# 05-Front_Panel_SFP_1.net
KiCad netlist of a schematic drawn in Altium Designer
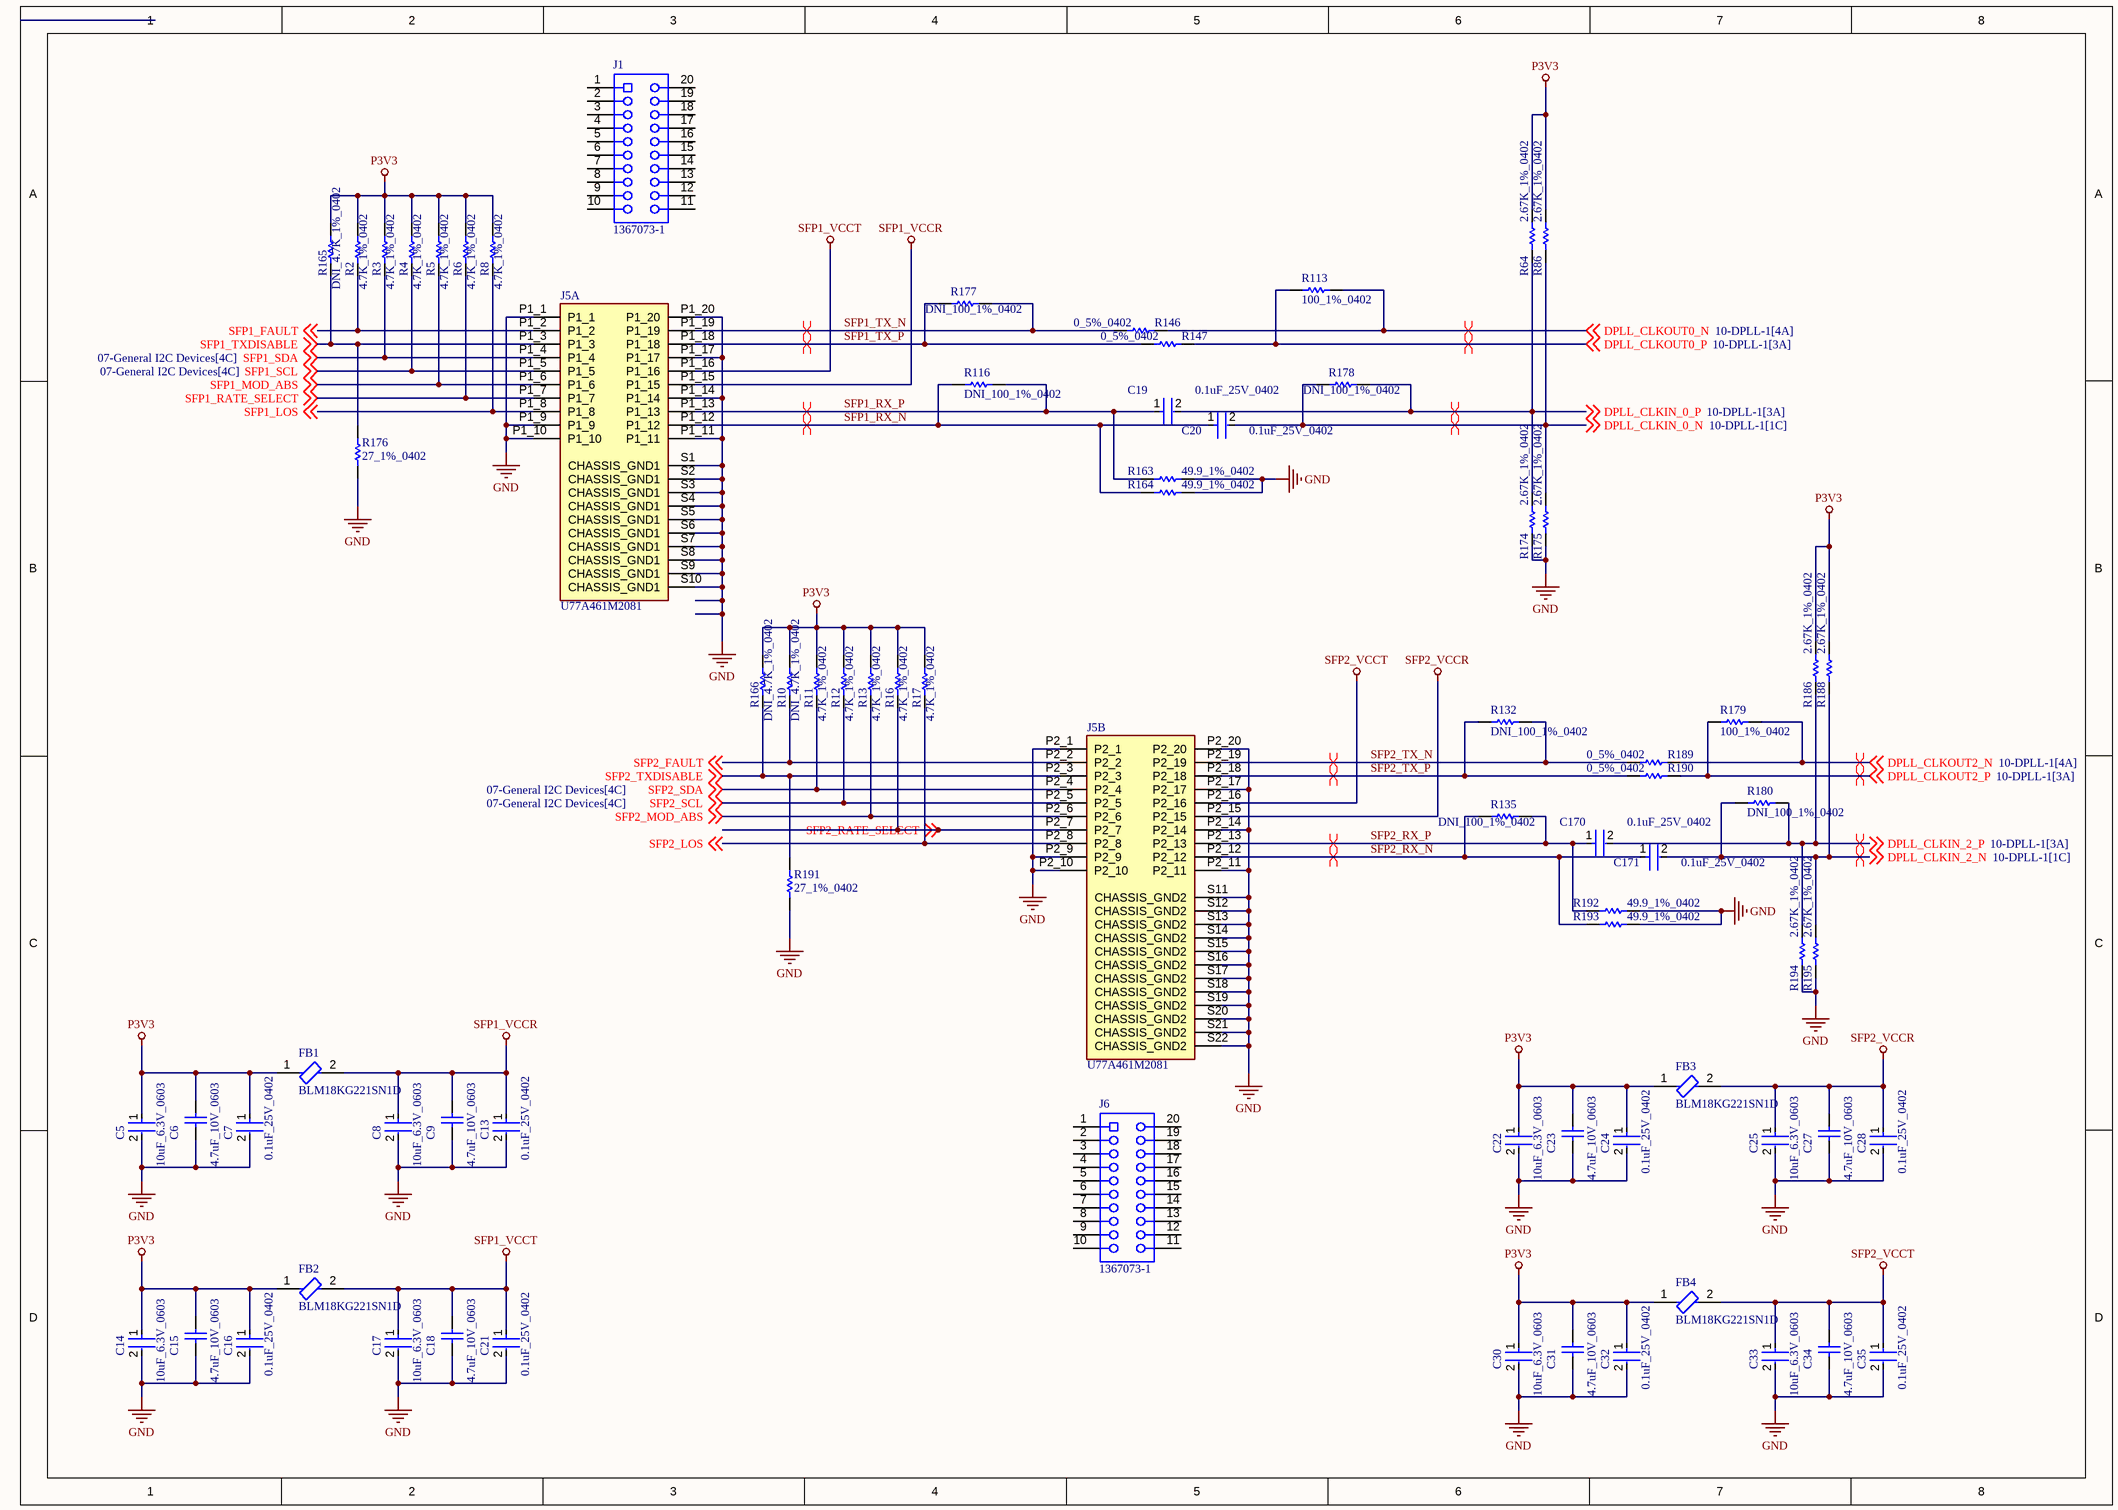
[diagram p0: 05-Front Panel SFP_1.SchDoc]

(export (version "E")
  (design (tool "Eeschema 10.0.6"))
  (components
    (comp (ref "C5")
      (value "10uF_6.3V_0603")
      (footprint "FP-C0603C106M9PACTU-MFG")
      (description "CAP CER 10UF 6.3V X5R 0603")
      (fields
        (field (name "MANUFACTURER PART NUMBER") "C0603C106M9PACTU")
        (field (name "MANUFACTURER") "Kemet")
      )
      (libsource (lib "Altium Content Vault") (part "b4654b650e69147ec39a6b967a45e02"))
    )
    (comp (ref "C6")
      (value "4.7uF_10V_0603")
      (footprint "CAPC1608X87X35NL15T15")
      (fields (field (name "PART NUMBER") "C0603C475K8PACTU") (field (name "MANUFACTURER") "Kemet"))
      (libsource (lib "Altium Content Vault") (part "CAP"))
    )
    (comp (ref "C7")
      (value "0.1uF_25V_0402")
      (footprint "FP-0402-L_1_0_1-W_0_5_0_1-IPC_C")
      (description "General Purpose Ceramic Capacitor, 0402, 100nF, 10%, X7R, 15%, 25V")
      (fields (field (name "VOLTAGE") "25V") (field (name "TOLERANCE") "10%"))
      (libsource (lib "Altium Content Vault") (part "b4654b650e69147ec39a6b967a45e02"))
    )
    (comp (ref "C8")
      (value "10uF_6.3V_0603")
      (footprint "FP-C0603C106M9PACTU-MFG")
      (description "CAP CER 10UF 6.3V X5R 0603")
      (fields
        (field (name "MANUFACTURER PART NUMBER") "C0603C106M9PACTU")
        (field (name "MANUFACTURER") "Kemet")
      )
      (libsource (lib "Altium Content Vault") (part "b4654b650e69147ec39a6b967a45e02"))
    )
    (comp (ref "C9")
      (value "4.7uF_10V_0603")
      (footprint "CAPC1608X87X35NL15T15")
      (fields (field (name "PART NUMBER") "C0603C475K8PACTU") (field (name "MANUFACTURER") "Kemet"))
      (libsource (lib "Altium Content Vault") (part "CAP"))
    )
    (comp (ref "C13")
      (value "0.1uF_25V_0402")
      (footprint "FP-0402-L_1_0_1-W_0_5_0_1-IPC_C")
      (description "General Purpose Ceramic Capacitor, 0402, 100nF, 10%, X7R, 15%, 25V")
      (fields (field (name "VOLTAGE") "25V") (field (name "TOLERANCE") "10%"))
      (libsource (lib "Altium Content Vault") (part "b4654b650e69147ec39a6b967a45e02"))
    )
    (comp (ref "C14")
      (value "10uF_6.3V_0603")
      (footprint "FP-C0603C106M9PACTU-MFG")
      (description "CAP CER 10UF 6.3V X5R 0603")
      (fields
        (field (name "MANUFACTURER PART NUMBER") "C0603C106M9PACTU")
        (field (name "MANUFACTURER") "Kemet")
      )
      (libsource (lib "Altium Content Vault") (part "b4654b650e69147ec39a6b967a45e02"))
    )
    (comp (ref "C15")
      (value "4.7uF_10V_0603")
      (footprint "CAPC1608X87X35NL15T15")
      (fields (field (name "PART NUMBER") "C0603C475K8PACTU") (field (name "MANUFACTURER") "Kemet"))
      (libsource (lib "Altium Content Vault") (part "CAP"))
    )
    (comp (ref "C16")
      (value "0.1uF_25V_0402")
      (footprint "FP-0402-L_1_0_1-W_0_5_0_1-IPC_C")
      (description "General Purpose Ceramic Capacitor, 0402, 100nF, 10%, X7R, 15%, 25V")
      (fields (field (name "VOLTAGE") "25V") (field (name "TOLERANCE") "10%"))
      (libsource (lib "Altium Content Vault") (part "b4654b650e69147ec39a6b967a45e02"))
    )
    (comp (ref "C17")
      (value "10uF_6.3V_0603")
      (footprint "FP-C0603C106M9PACTU-MFG")
      (description "CAP CER 10UF 6.3V X5R 0603")
      (fields
        (field (name "MANUFACTURER PART NUMBER") "C0603C106M9PACTU")
        (field (name "MANUFACTURER") "Kemet")
      )
      (libsource (lib "Altium Content Vault") (part "b4654b650e69147ec39a6b967a45e02"))
    )
    (comp (ref "C18")
      (value "4.7uF_10V_0603")
      (footprint "CAPC1608X87X35NL15T15")
      (fields (field (name "PART NUMBER") "C0603C475K8PACTU") (field (name "MANUFACTURER") "Kemet"))
      (libsource (lib "Altium Content Vault") (part "CAP"))
    )
    (comp (ref "C19")
      (value "0.1uF_25V_0402")
      (footprint "FP-0402-L_1_0_1-W_0_5_0_1-IPC_C")
      (description "General Purpose Ceramic Capacitor, 0402, 100nF, 10%, X7R, 15%, 25V")
      (fields (field (name "VOLTAGE") "25V") (field (name "TOLERANCE") "10%"))
      (libsource (lib "Altium Content Vault") (part "b4654b650e69147ec39a6b967a45e02"))
    )
    (comp (ref "C20")
      (value "0.1uF_25V_0402")
      (footprint "FP-0402-L_1_0_1-W_0_5_0_1-IPC_C")
      (description "General Purpose Ceramic Capacitor, 0402, 100nF, 10%, X7R, 15%, 25V")
      (fields (field (name "VOLTAGE") "25V") (field (name "TOLERANCE") "10%"))
      (libsource (lib "Altium Content Vault") (part "b4654b650e69147ec39a6b967a45e02"))
    )
    (comp (ref "C21")
      (value "0.1uF_25V_0402")
      (footprint "FP-0402-L_1_0_1-W_0_5_0_1-IPC_C")
      (description "General Purpose Ceramic Capacitor, 0402, 100nF, 10%, X7R, 15%, 25V")
      (fields (field (name "VOLTAGE") "25V") (field (name "TOLERANCE") "10%"))
      (libsource (lib "Altium Content Vault") (part "b4654b650e69147ec39a6b967a45e02"))
    )
    (comp (ref "C22")
      (value "10uF_6.3V_0603")
      (footprint "FP-C0603C106M9PACTU-MFG")
      (description "CAP CER 10UF 6.3V X5R 0603")
      (fields
        (field (name "MANUFACTURER PART NUMBER") "C0603C106M9PACTU")
        (field (name "MANUFACTURER") "Kemet")
      )
      (libsource (lib "Altium Content Vault") (part "b4654b650e69147ec39a6b967a45e02"))
    )
    (comp (ref "C23")
      (value "4.7uF_10V_0603")
      (footprint "CAPC1608X87X35NL15T15")
      (fields (field (name "PART NUMBER") "C0603C475K8PACTU") (field (name "MANUFACTURER") "Kemet"))
      (libsource (lib "Altium Content Vault") (part "CAP"))
    )
    (comp (ref "C24")
      (value "0.1uF_25V_0402")
      (footprint "FP-0402-L_1_0_1-W_0_5_0_1-IPC_C")
      (description "General Purpose Ceramic Capacitor, 0402, 100nF, 10%, X7R, 15%, 25V")
      (fields (field (name "VOLTAGE") "25V") (field (name "TOLERANCE") "10%"))
      (libsource (lib "Altium Content Vault") (part "b4654b650e69147ec39a6b967a45e02"))
    )
    (comp (ref "C25")
      (value "10uF_6.3V_0603")
      (footprint "FP-C0603C106M9PACTU-MFG")
      (description "CAP CER 10UF 6.3V X5R 0603")
      (fields
        (field (name "MANUFACTURER PART NUMBER") "C0603C106M9PACTU")
        (field (name "MANUFACTURER") "Kemet")
      )
      (libsource (lib "Altium Content Vault") (part "b4654b650e69147ec39a6b967a45e02"))
    )
    (comp (ref "C27")
      (value "4.7uF_10V_0603")
      (footprint "CAPC1608X87X35NL15T15")
      (fields (field (name "PART NUMBER") "C0603C475K8PACTU") (field (name "MANUFACTURER") "Kemet"))
      (libsource (lib "Altium Content Vault") (part "CAP"))
    )
    (comp (ref "C28")
      (value "0.1uF_25V_0402")
      (footprint "FP-0402-L_1_0_1-W_0_5_0_1-IPC_C")
      (description "General Purpose Ceramic Capacitor, 0402, 100nF, 10%, X7R, 15%, 25V")
      (fields (field (name "VOLTAGE") "25V") (field (name "TOLERANCE") "10%"))
      (libsource (lib "Altium Content Vault") (part "b4654b650e69147ec39a6b967a45e02"))
    )
    (comp (ref "C30")
      (value "10uF_6.3V_0603")
      (footprint "FP-C0603C106M9PACTU-MFG")
      (description "CAP CER 10UF 6.3V X5R 0603")
      (fields
        (field (name "MANUFACTURER PART NUMBER") "C0603C106M9PACTU")
        (field (name "MANUFACTURER") "Kemet")
      )
      (libsource (lib "Altium Content Vault") (part "b4654b650e69147ec39a6b967a45e02"))
    )
    (comp (ref "C31")
      (value "4.7uF_10V_0603")
      (footprint "CAPC1608X87X35NL15T15")
      (fields (field (name "PART NUMBER") "C0603C475K8PACTU") (field (name "MANUFACTURER") "Kemet"))
      (libsource (lib "Altium Content Vault") (part "CAP"))
    )
    (comp (ref "C32")
      (value "0.1uF_25V_0402")
      (footprint "FP-0402-L_1_0_1-W_0_5_0_1-IPC_C")
      (description "General Purpose Ceramic Capacitor, 0402, 100nF, 10%, X7R, 15%, 25V")
      (fields (field (name "VOLTAGE") "25V") (field (name "TOLERANCE") "10%"))
      (libsource (lib "Altium Content Vault") (part "b4654b650e69147ec39a6b967a45e02"))
    )
    (comp (ref "C33")
      (value "10uF_6.3V_0603")
      (footprint "FP-C0603C106M9PACTU-MFG")
      (description "CAP CER 10UF 6.3V X5R 0603")
      (fields
        (field (name "MANUFACTURER PART NUMBER") "C0603C106M9PACTU")
        (field (name "MANUFACTURER") "Kemet")
      )
      (libsource (lib "Altium Content Vault") (part "b4654b650e69147ec39a6b967a45e02"))
    )
    (comp (ref "C34")
      (value "4.7uF_10V_0603")
      (footprint "CAPC1608X87X35NL15T15")
      (fields (field (name "PART NUMBER") "C0603C475K8PACTU") (field (name "MANUFACTURER") "Kemet"))
      (libsource (lib "Altium Content Vault") (part "CAP"))
    )
    (comp (ref "C35")
      (value "0.1uF_25V_0402")
      (footprint "FP-0402-L_1_0_1-W_0_5_0_1-IPC_C")
      (description "General Purpose Ceramic Capacitor, 0402, 100nF, 10%, X7R, 15%, 25V")
      (fields (field (name "VOLTAGE") "25V") (field (name "TOLERANCE") "10%"))
      (libsource (lib "Altium Content Vault") (part "b4654b650e69147ec39a6b967a45e02"))
    )
    (comp (ref "C170")
      (value "0.1uF_25V_0402")
      (footprint "FP-0402-L_1_0_1-W_0_5_0_1-IPC_C")
      (description "General Purpose Ceramic Capacitor, 0402, 100nF, 10%, X7R, 15%, 25V")
      (fields (field (name "VOLTAGE") "25V") (field (name "TOLERANCE") "10%"))
      (libsource (lib "Altium Content Vault") (part "b4654b650e69147ec39a6b967a45e02"))
    )
    (comp (ref "C171")
      (value "0.1uF_25V_0402")
      (footprint "FP-0402-L_1_0_1-W_0_5_0_1-IPC_C")
      (description "General Purpose Ceramic Capacitor, 0402, 100nF, 10%, X7R, 15%, 25V")
      (fields (field (name "VOLTAGE") "25V") (field (name "TOLERANCE") "10%"))
      (libsource (lib "Altium Content Vault") (part "b4654b650e69147ec39a6b967a45e02"))
    )
    (comp (ref "FB1")
      (value "BLM18KG221SN1D")
      (footprint "FP-BLM18-0_15-t0_8-IPC_B")
      (description "Chip Ferrite Bead, 0603, 220Ω @ 100MHz, 0.05Ω, 25%, 2.2A")
      (fields (field (name "TOLERANCE") "25%"))
      (libsource (lib "Altium Content Vault") (part "5f30dd21d616792df468990f7003faa"))
    )
    (comp (ref "FB2")
      (value "BLM18KG221SN1D")
      (footprint "FP-BLM18-0_15-t0_8-IPC_B")
      (description "Chip Ferrite Bead, 0603, 220Ω @ 100MHz, 0.05Ω, 25%, 2.2A")
      (fields (field (name "TOLERANCE") "25%"))
      (libsource (lib "Altium Content Vault") (part "5f30dd21d616792df468990f7003faa"))
    )
    (comp (ref "FB3")
      (value "BLM18KG221SN1D")
      (footprint "FP-BLM18-0_15-t0_8-IPC_B")
      (description "Chip Ferrite Bead, 0603, 220Ω @ 100MHz, 0.05Ω, 25%, 2.2A")
      (fields (field (name "TOLERANCE") "25%"))
      (libsource (lib "Altium Content Vault") (part "5f30dd21d616792df468990f7003faa"))
    )
    (comp (ref "FB4")
      (value "BLM18KG221SN1D")
      (footprint "FP-BLM18-0_15-t0_8-IPC_B")
      (description "Chip Ferrite Bead, 0603, 220Ω @ 100MHz, 0.05Ω, 25%, 2.2A")
      (fields (field (name "TOLERANCE") "25%"))
      (libsource (lib "Altium Content Vault") (part "5f30dd21d616792df468990f7003faa"))
    )
    (comp (ref "J1")
      (value "1367073-1")
      (footprint "TECO-1367073-1_V")
      (fields (field (name "MANUFACTURER") "TE Connectivity"))
      (libsource (lib "Altium Content Vault") (part "CN-2P-F-R20_B"))
    )
    (comp (ref "J5")
      (value "U77A461M2081")
      (footprint "AMPHENOL_U77A461M2081")
      (fields (field (name "MF") "AMPHENOL ICC / FCI"))
      (libsource (lib "U77A461M2081") (part "U77A461M2081"))
    )
    (comp (ref "J6")
      (value "1367073-1")
      (footprint "TECO-1367073-1_V")
      (fields (field (name "MANUFACTURER") "TE Connectivity"))
      (libsource (lib "Altium Content Vault") (part "CN-2P-F-R20_B"))
    )
    (comp (ref "R2")
      (value "4.7K_1%_0402")
      (footprint "RESC1005X40X25NL10T10")
      (fields (field (name "MANUFACTURER") "Bourns") (field (name "PART NUMBER") "CR0402-FX-4701GLF"))
      (libsource (lib "Altium Content Vault") (part "RES"))
    )
    (comp (ref "R3")
      (value "4.7K_1%_0402")
      (footprint "RESC1005X40X25NL10T10")
      (fields (field (name "MANUFACTURER") "Bourns") (field (name "PART NUMBER") "CR0402-FX-4701GLF"))
      (libsource (lib "Altium Content Vault") (part "RES"))
    )
    (comp (ref "R4")
      (value "4.7K_1%_0402")
      (footprint "RESC1005X40X25NL10T10")
      (fields (field (name "MANUFACTURER") "Bourns") (field (name "PART NUMBER") "CR0402-FX-4701GLF"))
      (libsource (lib "Altium Content Vault") (part "RES"))
    )
    (comp (ref "R5")
      (value "4.7K_1%_0402")
      (footprint "RESC1005X40X25NL10T10")
      (fields (field (name "MANUFACTURER") "Bourns") (field (name "PART NUMBER") "CR0402-FX-4701GLF"))
      (libsource (lib "Altium Content Vault") (part "RES"))
    )
    (comp (ref "R6")
      (value "4.7K_1%_0402")
      (footprint "RESC1005X40X25NL10T10")
      (fields (field (name "MANUFACTURER") "Bourns") (field (name "PART NUMBER") "CR0402-FX-4701GLF"))
      (libsource (lib "Altium Content Vault") (part "RES"))
    )
    (comp (ref "R8")
      (value "4.7K_1%_0402")
      (footprint "RESC1005X40X25NL10T10")
      (fields (field (name "MANUFACTURER") "Bourns") (field (name "PART NUMBER") "CR0402-FX-4701GLF"))
      (libsource (lib "Altium Content Vault") (part "RES"))
    )
    (comp (ref "R10")
      (value "DNI_4.7K_1%_0402")
      (footprint "RESC1005X40X25NL10T10")
      (fields (field (name "MANUFACTURER") "Bourns") (field (name "PART NUMBER") "CR0402-FX-4701GLF"))
      (libsource (lib "Altium Content Vault") (part "RES"))
    )
    (comp (ref "R11")
      (value "4.7K_1%_0402")
      (footprint "RESC1005X40X25NL10T10")
      (fields (field (name "MANUFACTURER") "Bourns") (field (name "PART NUMBER") "CR0402-FX-4701GLF"))
      (libsource (lib "Altium Content Vault") (part "RES"))
    )
    (comp (ref "R12")
      (value "4.7K_1%_0402")
      (footprint "RESC1005X40X25NL10T10")
      (fields (field (name "MANUFACTURER") "Bourns") (field (name "PART NUMBER") "CR0402-FX-4701GLF"))
      (libsource (lib "Altium Content Vault") (part "RES"))
    )
    (comp (ref "R13")
      (value "4.7K_1%_0402")
      (footprint "RESC1005X40X25NL10T10")
      (fields (field (name "MANUFACTURER") "Bourns") (field (name "PART NUMBER") "CR0402-FX-4701GLF"))
      (libsource (lib "Altium Content Vault") (part "RES"))
    )
    (comp (ref "R16")
      (value "4.7K_1%_0402")
      (footprint "RESC1005X40X25NL10T10")
      (fields (field (name "MANUFACTURER") "Bourns") (field (name "PART NUMBER") "CR0402-FX-4701GLF"))
      (libsource (lib "Altium Content Vault") (part "RES"))
    )
    (comp (ref "R17")
      (value "4.7K_1%_0402")
      (footprint "RESC1005X40X25NL10T10")
      (fields (field (name "MANUFACTURER") "Bourns") (field (name "PART NUMBER") "CR0402-FX-4701GLF"))
      (libsource (lib "Altium Content Vault") (part "RES"))
    )
    (comp (ref "R64")
      (value "2.67K_1%_0402")
      (footprint "RESC1005X40X25NL05T10")
      (fields (field (name "MANUFACTURER") "Yageo") (field (name "PART NUMBER") "RC0402FR-072K67L"))
      (libsource (lib "Altium Content Vault") (part "RES"))
    )
    (comp (ref "R86")
      (value "2.67K_1%_0402")
      (footprint "RESC1005X40X25NL05T10")
      (fields (field (name "MANUFACTURER") "Yageo") (field (name "PART NUMBER") "RC0402FR-072K67L"))
      (libsource (lib "Altium Content Vault") (part "RES"))
    )
    (comp (ref "R113")
      (value "100_1%_0402")
      (footprint "RESC1005X40X25NL05T10")
      (fields (field (name "MANUFACTURER") "Yageo") (field (name "PART NUMBER") "RC0402FR-13100RL"))
      (libsource (lib "Altium Content Vault") (part "RES"))
    )
    (comp (ref "R116")
      (value "DNI_100_1%_0402")
      (footprint "RESC1005X40X25NL05T10")
      (fields (field (name "MANUFACTURER") "Yageo") (field (name "PART NUMBER") "RC0402FR-13100RL"))
      (libsource (lib "Altium Content Vault") (part "RES"))
    )
    (comp (ref "R132")
      (value "DNI_100_1%_0402")
      (footprint "RESC1005X40X25NL05T10")
      (fields (field (name "MANUFACTURER") "Yageo") (field (name "PART NUMBER") "RC0402FR-13100RL"))
      (libsource (lib "Altium Content Vault") (part "RES"))
    )
    (comp (ref "R135")
      (value "DNI_100_1%_0402")
      (footprint "RESC1005X40X25NL05T10")
      (fields (field (name "MANUFACTURER") "Yageo") (field (name "PART NUMBER") "RC0402FR-13100RL"))
      (libsource (lib "Altium Content Vault") (part "RES"))
    )
    (comp (ref "R146")
      (value "0_5%_0402")
      (footprint "RESC1005X40X25LL10T10")
      (fields (field (name "MANUFACTURER") "KOA Speer") (field (name "PART NUMBER") "RK73Z1ETTP"))
      (libsource (lib "Altium Content Vault") (part "RES"))
    )
    (comp (ref "R147")
      (value "0_5%_0402")
      (footprint "RESC1005X40X25LL10T10")
      (fields (field (name "MANUFACTURER") "KOA Speer") (field (name "PART NUMBER") "RK73Z1ETTP"))
      (libsource (lib "Altium Content Vault") (part "RES"))
    )
    (comp (ref "R163")
      (value "49.9_1%_0402")
      (footprint "RESC1005X40X25NL10T10")
      (fields (field (name "PART NUMBER") "RK73H1ETTP49R9F") (field (name "MANUFACTURER") "KOA Speer"))
      (libsource (lib "Altium Content Vault") (part "RES"))
    )
    (comp (ref "R164")
      (value "49.9_1%_0402")
      (footprint "RESC1005X40X25NL10T10")
      (fields (field (name "PART NUMBER") "RK73H1ETTP49R9F") (field (name "MANUFACTURER") "KOA Speer"))
      (libsource (lib "Altium Content Vault") (part "RES"))
    )
    (comp (ref "R165")
      (value "DNI_4.7K_1%_0402")
      (footprint "RESC1005X40X25NL10T10")
      (fields (field (name "MANUFACTURER") "Bourns") (field (name "PART NUMBER") "CR0402-FX-4701GLF"))
      (libsource (lib "Altium Content Vault") (part "RES"))
    )
    (comp (ref "R166")
      (value "DNI_4.7K_1%_0402")
      (footprint "RESC1005X40X25NL10T10")
      (fields (field (name "MANUFACTURER") "Bourns") (field (name "PART NUMBER") "CR0402-FX-4701GLF"))
      (libsource (lib "Altium Content Vault") (part "RES"))
    )
    (comp (ref "R174")
      (value "2.67K_1%_0402")
      (footprint "RESC1005X40X25NL05T10")
      (fields (field (name "MANUFACTURER") "Yageo") (field (name "PART NUMBER") "RC0402FR-072K67L"))
      (libsource (lib "Altium Content Vault") (part "RES"))
    )
    (comp (ref "R175")
      (value "2.67K_1%_0402")
      (footprint "RESC1005X40X25NL05T10")
      (fields (field (name "MANUFACTURER") "Yageo") (field (name "PART NUMBER") "RC0402FR-072K67L"))
      (libsource (lib "Altium Content Vault") (part "RES"))
    )
    (comp (ref "R176")
      (value "27_1%_0402")
      (footprint "RESC1005X40X25NL05T05")
      (fields (field (name "PART NUMBER") "CRCW040227R0FKED") (field (name "MANUFACTURER") "Vishay Dale"))
      (libsource (lib "Altium Content Vault") (part "RES"))
    )
    (comp (ref "R177")
      (value "DNI_100_1%_0402")
      (footprint "RESC1005X40X25NL05T10")
      (fields (field (name "MANUFACTURER") "Yageo") (field (name "PART NUMBER") "RC0402FR-13100RL"))
      (libsource (lib "Altium Content Vault") (part "RES"))
    )
    (comp (ref "R178")
      (value "DNI_100_1%_0402")
      (footprint "RESC1005X40X25NL05T10")
      (fields (field (name "MANUFACTURER") "Yageo") (field (name "PART NUMBER") "RC0402FR-13100RL"))
      (libsource (lib "Altium Content Vault") (part "RES"))
    )
    (comp (ref "R179")
      (value "100_1%_0402")
      (footprint "RESC1005X40X25NL05T10")
      (fields (field (name "MANUFACTURER") "Yageo") (field (name "PART NUMBER") "RC0402FR-13100RL"))
      (libsource (lib "Altium Content Vault") (part "RES"))
    )
    (comp (ref "R180")
      (value "DNI_100_1%_0402")
      (footprint "RESC1005X40X25NL05T10")
      (fields (field (name "MANUFACTURER") "Yageo") (field (name "PART NUMBER") "RC0402FR-13100RL"))
      (libsource (lib "Altium Content Vault") (part "RES"))
    )
    (comp (ref "R186")
      (value "2.67K_1%_0402")
      (footprint "RESC1005X40X25NL05T10")
      (fields (field (name "MANUFACTURER") "Yageo") (field (name "PART NUMBER") "RC0402FR-072K67L"))
      (libsource (lib "Altium Content Vault") (part "RES"))
    )
    (comp (ref "R188")
      (value "2.67K_1%_0402")
      (footprint "RESC1005X40X25NL05T10")
      (fields (field (name "MANUFACTURER") "Yageo") (field (name "PART NUMBER") "RC0402FR-072K67L"))
      (libsource (lib "Altium Content Vault") (part "RES"))
    )
    (comp (ref "R189")
      (value "0_5%_0402")
      (footprint "RESC1005X40X25LL10T10")
      (fields (field (name "MANUFACTURER") "KOA Speer") (field (name "PART NUMBER") "RK73Z1ETTP"))
      (libsource (lib "Altium Content Vault") (part "RES"))
    )
    (comp (ref "R190")
      (value "0_5%_0402")
      (footprint "RESC1005X40X25LL10T10")
      (fields (field (name "MANUFACTURER") "KOA Speer") (field (name "PART NUMBER") "RK73Z1ETTP"))
      (libsource (lib "Altium Content Vault") (part "RES"))
    )
    (comp (ref "R191")
      (value "27_1%_0402")
      (footprint "RESC1005X40X25NL05T05")
      (fields (field (name "PART NUMBER") "CRCW040227R0FKED") (field (name "MANUFACTURER") "Vishay Dale"))
      (libsource (lib "Altium Content Vault") (part "RES"))
    )
    (comp (ref "R192")
      (value "49.9_1%_0402")
      (footprint "RESC1005X40X25NL10T10")
      (fields (field (name "PART NUMBER") "RK73H1ETTP49R9F") (field (name "MANUFACTURER") "KOA Speer"))
      (libsource (lib "Altium Content Vault") (part "RES"))
    )
    (comp (ref "R193")
      (value "49.9_1%_0402")
      (footprint "RESC1005X40X25NL10T10")
      (fields (field (name "PART NUMBER") "RK73H1ETTP49R9F") (field (name "MANUFACTURER") "KOA Speer"))
      (libsource (lib "Altium Content Vault") (part "RES"))
    )
    (comp (ref "R194")
      (value "2.67K_1%_0402")
      (footprint "RESC1005X40X25NL05T10")
      (fields (field (name "MANUFACTURER") "Yageo") (field (name "PART NUMBER") "RC0402FR-072K67L"))
      (libsource (lib "Altium Content Vault") (part "RES"))
    )
    (comp (ref "R195")
      (value "2.67K_1%_0402")
      (footprint "RESC1005X40X25NL05T10")
      (fields (field (name "MANUFACTURER") "Yageo") (field (name "PART NUMBER") "RC0402FR-072K67L"))
      (libsource (lib "Altium Content Vault") (part "RES"))
    )
  )
  (nets
    (net (code "1") (name "/SFP1_RX_N") (class "Default")
      (node (ref "C20") (pin "1") (pinfunction "1_1") (pintype "passive"))
      (node (ref "J5") (pin "P1_12") (pinfunction "P1_12_P1_12") (pintype "passive"))
      (node (ref "R116") (pin "1") (pinfunction "1_1") (pintype "passive"))
      (node (ref "R164") (pin "1") (pinfunction "1_1") (pintype "passive"))
    )
    (net (code "2") (name "/SFP1_RX_P") (class "Default")
      (node (ref "C19") (pin "1") (pinfunction "1_1") (pintype "passive"))
      (node (ref "J5") (pin "P1_13") (pinfunction "P1_13_P1_13") (pintype "passive"))
      (node (ref "R116") (pin "2") (pinfunction "2_2") (pintype "passive"))
      (node (ref "R163") (pin "1") (pinfunction "1_1") (pintype "passive"))
    )
    (net (code "3") (name "/SFP1_TX_N") (class "Default")
      (node (ref "J5") (pin "P1_19") (pinfunction "P1_19_P1_19") (pintype "passive"))
      (node (ref "R146") (pin "1") (pinfunction "1_1") (pintype "passive"))
      (node (ref "R177") (pin "2") (pinfunction "2_2") (pintype "passive"))
    )
    (net (code "4") (name "/SFP1_TX_P") (class "Default")
      (node (ref "J5") (pin "P1_18") (pinfunction "P1_18_P1_18") (pintype "passive"))
      (node (ref "R147") (pin "1") (pinfunction "1_1") (pintype "passive"))
      (node (ref "R177") (pin "1") (pinfunction "1_1") (pintype "passive"))
    )
    (net (code "5") (name "/SFP2_RX_N") (class "Default")
      (node (ref "C171") (pin "1") (pinfunction "1_1") (pintype "passive"))
      (node (ref "J5") (pin "P2_12") (pinfunction "P2_12_P2_12") (pintype "passive"))
      (node (ref "R135") (pin "1") (pinfunction "1_1") (pintype "passive"))
      (node (ref "R193") (pin "1") (pinfunction "1_1") (pintype "passive"))
    )
    (net (code "6") (name "/SFP2_RX_P") (class "Default")
      (node (ref "C170") (pin "1") (pinfunction "1_1") (pintype "passive"))
      (node (ref "J5") (pin "P2_13") (pinfunction "P2_13_P2_13") (pintype "passive"))
      (node (ref "R135") (pin "2") (pinfunction "2_2") (pintype "passive"))
      (node (ref "R192") (pin "1") (pinfunction "1_1") (pintype "passive"))
    )
    (net (code "7") (name "/SFP2_TX_N") (class "Default")
      (node (ref "J5") (pin "P2_19") (pinfunction "P2_19_P2_19") (pintype "passive"))
      (node (ref "R132") (pin "2") (pinfunction "2_2") (pintype "passive"))
      (node (ref "R189") (pin "1") (pinfunction "1_1") (pintype "passive"))
    )
    (net (code "8") (name "/SFP2_TX_P") (class "Default")
      (node (ref "J5") (pin "P2_18") (pinfunction "P2_18_P2_18") (pintype "passive"))
      (node (ref "R132") (pin "1") (pinfunction "1_1") (pintype "passive"))
      (node (ref "R190") (pin "1") (pinfunction "1_1") (pintype "passive"))
    )
    (net (code "9") (name "DPLL_CLKIN_0_N") (class "Default")
      (node (ref "C20") (pin "2") (pinfunction "2_2") (pintype "passive"))
      (node (ref "R175") (pin "2") (pinfunction "2_2") (pintype "passive"))
      (node (ref "R178") (pin "1") (pinfunction "1_1") (pintype "passive"))
      (node (ref "R86") (pin "1") (pinfunction "1_1") (pintype "passive"))
    )
    (net (code "10") (name "DPLL_CLKIN_0_P") (class "Default")
      (node (ref "C19") (pin "2") (pinfunction "2_2") (pintype "passive"))
      (node (ref "R174") (pin "2") (pinfunction "2_2") (pintype "passive"))
      (node (ref "R178") (pin "2") (pinfunction "2_2") (pintype "passive"))
      (node (ref "R64") (pin "1") (pinfunction "1_1") (pintype "passive"))
    )
    (net (code "11") (name "DPLL_CLKIN_2_N") (class "Default")
      (node (ref "C171") (pin "2") (pinfunction "2_2") (pintype "passive"))
      (node (ref "R180") (pin "1") (pinfunction "1_1") (pintype "passive"))
      (node (ref "R188") (pin "1") (pinfunction "1_1") (pintype "passive"))
      (node (ref "R195") (pin "2") (pinfunction "2_2") (pintype "passive"))
    )
    (net (code "12") (name "DPLL_CLKIN_2_P") (class "Default")
      (node (ref "C170") (pin "2") (pinfunction "2_2") (pintype "passive"))
      (node (ref "R180") (pin "2") (pinfunction "2_2") (pintype "passive"))
      (node (ref "R186") (pin "1") (pinfunction "1_1") (pintype "passive"))
      (node (ref "R194") (pin "2") (pinfunction "2_2") (pintype "passive"))
    )
    (net (code "13") (name "DPLL_CLKOUT0_N") (class "Default")
      (node (ref "R113") (pin "2") (pinfunction "2_2") (pintype "passive"))
      (node (ref "R146") (pin "2") (pinfunction "2_2") (pintype "passive"))
    )
    (net (code "14") (name "DPLL_CLKOUT0_P") (class "Default")
      (node (ref "R113") (pin "1") (pinfunction "1_1") (pintype "passive"))
      (node (ref "R147") (pin "2") (pinfunction "2_2") (pintype "passive"))
    )
    (net (code "15") (name "DPLL_CLKOUT2_N") (class "Default")
      (node (ref "R179") (pin "2") (pinfunction "2_2") (pintype "passive"))
      (node (ref "R189") (pin "2") (pinfunction "2_2") (pintype "passive"))
    )
    (net (code "16") (name "DPLL_CLKOUT2_P") (class "Default")
      (node (ref "R179") (pin "1") (pinfunction "1_1") (pintype "passive"))
      (node (ref "R190") (pin "2") (pinfunction "2_2") (pintype "passive"))
    )
    (net (code "17") (name "GND") (class "Default")
      (node (ref "C13") (pin "2") (pinfunction "2_2") (pintype "passive"))
      (node (ref "C14") (pin "2") (pinfunction "2_2") (pintype "passive"))
      (node (ref "C15") (pin "1") (pinfunction "1_1") (pintype "passive"))
      (node (ref "C16") (pin "2") (pinfunction "2_2") (pintype "passive"))
      (node (ref "C17") (pin "2") (pinfunction "2_2") (pintype "passive"))
      (node (ref "C18") (pin "1") (pinfunction "1_1") (pintype "passive"))
      (node (ref "C21") (pin "2") (pinfunction "2_2") (pintype "passive"))
      (node (ref "C22") (pin "2") (pinfunction "2_2") (pintype "passive"))
      (node (ref "C23") (pin "1") (pinfunction "1_1") (pintype "passive"))
      (node (ref "C24") (pin "2") (pinfunction "2_2") (pintype "passive"))
      (node (ref "C25") (pin "2") (pinfunction "2_2") (pintype "passive"))
      (node (ref "C27") (pin "1") (pinfunction "1_1") (pintype "passive"))
      (node (ref "C28") (pin "2") (pinfunction "2_2") (pintype "passive"))
      (node (ref "C30") (pin "2") (pinfunction "2_2") (pintype "passive"))
      (node (ref "C31") (pin "1") (pinfunction "1_1") (pintype "passive"))
      (node (ref "C32") (pin "2") (pinfunction "2_2") (pintype "passive"))
      (node (ref "C33") (pin "2") (pinfunction "2_2") (pintype "passive"))
      (node (ref "C34") (pin "1") (pinfunction "1_1") (pintype "passive"))
      (node (ref "C35") (pin "2") (pinfunction "2_2") (pintype "passive"))
      (node (ref "C5") (pin "2") (pinfunction "2_2") (pintype "passive"))
      (node (ref "C6") (pin "1") (pinfunction "1_1") (pintype "passive"))
      (node (ref "C7") (pin "2") (pinfunction "2_2") (pintype "passive"))
      (node (ref "C8") (pin "2") (pinfunction "2_2") (pintype "passive"))
      (node (ref "C9") (pin "1") (pinfunction "1_1") (pintype "passive"))
      (node (ref "J5") (pin "P1_1") (pinfunction "P1_1_P1_1") (pintype "passive"))
      (node (ref "J5") (pin "P1_10") (pinfunction "P1_10_P1_10") (pintype "passive"))
      (node (ref "J5") (pin "P1_11") (pinfunction "P1_11_P1_11") (pintype "passive"))
      (node (ref "J5") (pin "P1_14") (pinfunction "P1_14_P1_14") (pintype "passive"))
      (node (ref "J5") (pin "P1_17") (pinfunction "P1_17_P1_17") (pintype "passive"))
      (node (ref "J5") (pin "P1_20") (pinfunction "P1_20_P1_20") (pintype "passive"))
      (node (ref "J5") (pin "P1_9") (pinfunction "P1_9_P1_9") (pintype "passive"))
      (node (ref "J5") (pin "P2_1") (pinfunction "P2_1_P2_1") (pintype "passive"))
      (node (ref "J5") (pin "P2_10") (pinfunction "P2_10_P2_10") (pintype "passive"))
      (node (ref "J5") (pin "P2_11") (pinfunction "P2_11_P2_11") (pintype "passive"))
      (node (ref "J5") (pin "P2_14") (pinfunction "P2_14_P2_14") (pintype "passive"))
      (node (ref "J5") (pin "P2_17") (pinfunction "P2_17_P2_17") (pintype "passive"))
      (node (ref "J5") (pin "P2_20") (pinfunction "P2_20_P2_20") (pintype "passive"))
      (node (ref "J5") (pin "P2_9") (pinfunction "P2_9_P2_9") (pintype "passive"))
      (node (ref "J5") (pin "S1") (pinfunction "CHASSIS_GND1_S1") (pintype "power_in"))
      (node (ref "J5") (pin "S10") (pinfunction "CHASSIS_GND1_S10") (pintype "power_in"))
      (node (ref "J5") (pin "S11") (pinfunction "CHASSIS_GND2_S11") (pintype "passive"))
      (node (ref "J5") (pin "S12") (pinfunction "CHASSIS_GND2_S12") (pintype "passive"))
      (node (ref "J5") (pin "S13") (pinfunction "CHASSIS_GND2_S13") (pintype "passive"))
      (node (ref "J5") (pin "S14") (pinfunction "CHASSIS_GND2_S14") (pintype "passive"))
      (node (ref "J5") (pin "S15") (pinfunction "CHASSIS_GND2_S15") (pintype "passive"))
      (node (ref "J5") (pin "S16") (pinfunction "CHASSIS_GND2_S16") (pintype "passive"))
      (node (ref "J5") (pin "S17") (pinfunction "CHASSIS_GND2_S17") (pintype "passive"))
      (node (ref "J5") (pin "S18") (pinfunction "CHASSIS_GND2_S18") (pintype "passive"))
      (node (ref "J5") (pin "S19") (pinfunction "CHASSIS_GND2_S19") (pintype "passive"))
      (node (ref "J5") (pin "S2") (pinfunction "CHASSIS_GND1_S2") (pintype "power_in"))
      (node (ref "J5") (pin "S20") (pinfunction "CHASSIS_GND2_S20") (pintype "passive"))
      (node (ref "J5") (pin "S21") (pinfunction "CHASSIS_GND2_S21") (pintype "passive"))
      (node (ref "J5") (pin "S22") (pinfunction "CHASSIS_GND2_S22") (pintype "passive"))
      (node (ref "J5") (pin "S3") (pinfunction "CHASSIS_GND1_S3") (pintype "power_in"))
      (node (ref "J5") (pin "S4") (pinfunction "CHASSIS_GND1_S4") (pintype "power_in"))
      (node (ref "J5") (pin "S5") (pinfunction "CHASSIS_GND1_S5") (pintype "power_in"))
      (node (ref "J5") (pin "S6") (pinfunction "CHASSIS_GND1_S6") (pintype "power_in"))
      (node (ref "J5") (pin "S7") (pinfunction "CHASSIS_GND1_S7") (pintype "power_in"))
      (node (ref "J5") (pin "S8") (pinfunction "CHASSIS_GND1_S8") (pintype "power_in"))
      (node (ref "J5") (pin "S9") (pinfunction "CHASSIS_GND1_S9") (pintype "power_in"))
      (node (ref "R163") (pin "2") (pinfunction "2_2") (pintype "passive"))
      (node (ref "R164") (pin "2") (pinfunction "2_2") (pintype "passive"))
      (node (ref "R174") (pin "1") (pinfunction "1_1") (pintype "passive"))
      (node (ref "R175") (pin "1") (pinfunction "1_1") (pintype "passive"))
      (node (ref "R176") (pin "1") (pinfunction "1_1") (pintype "passive"))
      (node (ref "R191") (pin "1") (pinfunction "1_1") (pintype "passive"))
      (node (ref "R192") (pin "2") (pinfunction "2_2") (pintype "passive"))
      (node (ref "R193") (pin "2") (pinfunction "2_2") (pintype "passive"))
      (node (ref "R194") (pin "1") (pinfunction "1_1") (pintype "passive"))
      (node (ref "R195") (pin "1") (pinfunction "1_1") (pintype "passive"))
    )
    (net (code "18") (name "P3V3") (class "Default")
      (node (ref "C14") (pin "1") (pinfunction "1_1") (pintype "passive"))
      (node (ref "C15") (pin "2") (pinfunction "2_2") (pintype "passive"))
      (node (ref "C16") (pin "1") (pinfunction "1_1") (pintype "passive"))
      (node (ref "C22") (pin "1") (pinfunction "1_1") (pintype "passive"))
      (node (ref "C23") (pin "2") (pinfunction "2_2") (pintype "passive"))
      (node (ref "C24") (pin "1") (pinfunction "1_1") (pintype "passive"))
      (node (ref "C30") (pin "1") (pinfunction "1_1") (pintype "passive"))
      (node (ref "C31") (pin "2") (pinfunction "2_2") (pintype "passive"))
      (node (ref "C32") (pin "1") (pinfunction "1_1") (pintype "passive"))
      (node (ref "C5") (pin "1") (pinfunction "1_1") (pintype "passive"))
      (node (ref "C6") (pin "2") (pinfunction "2_2") (pintype "passive"))
      (node (ref "C7") (pin "1") (pinfunction "1_1") (pintype "passive"))
      (node (ref "FB1") (pin "1") (pinfunction "1_1") (pintype "passive"))
      (node (ref "FB2") (pin "1") (pinfunction "1_1") (pintype "passive"))
      (node (ref "FB3") (pin "1") (pinfunction "1_1") (pintype "passive"))
      (node (ref "FB4") (pin "1") (pinfunction "1_1") (pintype "passive"))
      (node (ref "R10") (pin "1") (pinfunction "1_1") (pintype "passive"))
      (node (ref "R11") (pin "1") (pinfunction "1_1") (pintype "passive"))
      (node (ref "R12") (pin "1") (pinfunction "1_1") (pintype "passive"))
      (node (ref "R13") (pin "1") (pinfunction "1_1") (pintype "passive"))
      (node (ref "R16") (pin "1") (pinfunction "1_1") (pintype "passive"))
      (node (ref "R165") (pin "1") (pinfunction "1_1") (pintype "passive"))
      (node (ref "R166") (pin "1") (pinfunction "1_1") (pintype "passive"))
      (node (ref "R17") (pin "1") (pinfunction "1_1") (pintype "passive"))
      (node (ref "R186") (pin "2") (pinfunction "2_2") (pintype "passive"))
      (node (ref "R188") (pin "2") (pinfunction "2_2") (pintype "passive"))
      (node (ref "R2") (pin "1") (pinfunction "1_1") (pintype "passive"))
      (node (ref "R3") (pin "1") (pinfunction "1_1") (pintype "passive"))
      (node (ref "R4") (pin "1") (pinfunction "1_1") (pintype "passive"))
      (node (ref "R5") (pin "1") (pinfunction "1_1") (pintype "passive"))
      (node (ref "R6") (pin "1") (pinfunction "1_1") (pintype "passive"))
      (node (ref "R64") (pin "2") (pinfunction "2_2") (pintype "passive"))
      (node (ref "R8") (pin "1") (pinfunction "1_1") (pintype "passive"))
      (node (ref "R86") (pin "2") (pinfunction "2_2") (pintype "passive"))
    )
    (net (code "19") (name "SFP1_FAULT") (class "Default")
      (node (ref "J5") (pin "P1_2") (pinfunction "P1_2_P1_2") (pintype "passive"))
      (node (ref "R2") (pin "2") (pinfunction "2_2") (pintype "passive"))
    )
    (net (code "20") (name "SFP1_LOS") (class "Default")
      (node (ref "J5") (pin "P1_8") (pinfunction "P1_8_P1_8") (pintype "passive"))
      (node (ref "R8") (pin "2") (pinfunction "2_2") (pintype "passive"))
    )
    (net (code "21") (name "SFP1_MOD_ABS") (class "Default")
      (node (ref "J5") (pin "P1_6") (pinfunction "P1_6_P1_6") (pintype "passive"))
      (node (ref "R5") (pin "2") (pinfunction "2_2") (pintype "passive"))
    )
    (net (code "22") (name "SFP1_RATE_SELECT") (class "Default")
      (node (ref "J5") (pin "P1_7") (pinfunction "P1_7_P1_7") (pintype "passive"))
      (node (ref "R6") (pin "2") (pinfunction "2_2") (pintype "passive"))
    )
    (net (code "23") (name "SFP1_SCL") (class "Default")
      (node (ref "J5") (pin "P1_5") (pinfunction "P1_5_P1_5") (pintype "passive"))
      (node (ref "R4") (pin "2") (pinfunction "2_2") (pintype "passive"))
    )
    (net (code "24") (name "SFP1_SDA") (class "Default")
      (node (ref "J5") (pin "P1_4") (pinfunction "P1_4_P1_4") (pintype "passive"))
      (node (ref "R3") (pin "2") (pinfunction "2_2") (pintype "passive"))
    )
    (net (code "25") (name "SFP1_TXDISABLE") (class "Default")
      (node (ref "J5") (pin "P1_3") (pinfunction "P1_3_P1_3") (pintype "passive"))
      (node (ref "R165") (pin "2") (pinfunction "2_2") (pintype "passive"))
      (node (ref "R176") (pin "2") (pinfunction "2_2") (pintype "passive"))
    )
    (net (code "26") (name "SFP1_VCCR") (class "Default")
      (node (ref "C13") (pin "1") (pinfunction "1_1") (pintype "passive"))
      (node (ref "C8") (pin "1") (pinfunction "1_1") (pintype "passive"))
      (node (ref "C9") (pin "2") (pinfunction "2_2") (pintype "passive"))
      (node (ref "FB1") (pin "2") (pinfunction "2_2") (pintype "passive"))
      (node (ref "J5") (pin "P1_15") (pinfunction "P1_15_P1_15") (pintype "passive"))
    )
    (net (code "27") (name "SFP1_VCCT") (class "Default")
      (node (ref "C17") (pin "1") (pinfunction "1_1") (pintype "passive"))
      (node (ref "C18") (pin "2") (pinfunction "2_2") (pintype "passive"))
      (node (ref "C21") (pin "1") (pinfunction "1_1") (pintype "passive"))
      (node (ref "FB2") (pin "2") (pinfunction "2_2") (pintype "passive"))
      (node (ref "J5") (pin "P1_16") (pinfunction "P1_16_P1_16") (pintype "passive"))
    )
    (net (code "28") (name "SFP2_FAULT") (class "Default")
      (node (ref "J5") (pin "P2_2") (pinfunction "P2_2_P2_2") (pintype "passive"))
      (node (ref "R10") (pin "2") (pinfunction "2_2") (pintype "passive"))
    )
    (net (code "29") (name "SFP2_LOS") (class "Default")
      (node (ref "J5") (pin "P2_8") (pinfunction "P2_8_P2_8") (pintype "passive"))
      (node (ref "R17") (pin "2") (pinfunction "2_2") (pintype "passive"))
    )
    (net (code "30") (name "SFP2_MOD_ABS") (class "Default")
      (node (ref "J5") (pin "P2_6") (pinfunction "P2_6_P2_6") (pintype "passive"))
      (node (ref "R13") (pin "2") (pinfunction "2_2") (pintype "passive"))
    )
    (net (code "31") (name "SFP2_RATE_SELECT") (class "Default")
      (node (ref "J5") (pin "P2_7") (pinfunction "P2_7_P2_7") (pintype "passive"))
      (node (ref "R16") (pin "2") (pinfunction "2_2") (pintype "passive"))
    )
    (net (code "32") (name "SFP2_SCL") (class "Default")
      (node (ref "J5") (pin "P2_5") (pinfunction "P2_5_P2_5") (pintype "passive"))
      (node (ref "R12") (pin "2") (pinfunction "2_2") (pintype "passive"))
    )
    (net (code "33") (name "SFP2_SDA") (class "Default")
      (node (ref "J5") (pin "P2_4") (pinfunction "P2_4_P2_4") (pintype "passive"))
      (node (ref "R11") (pin "2") (pinfunction "2_2") (pintype "passive"))
    )
    (net (code "34") (name "SFP2_TXDISABLE") (class "Default")
      (node (ref "J5") (pin "P2_3") (pinfunction "P2_3_P2_3") (pintype "passive"))
      (node (ref "R166") (pin "2") (pinfunction "2_2") (pintype "passive"))
      (node (ref "R191") (pin "2") (pinfunction "2_2") (pintype "passive"))
    )
    (net (code "35") (name "SFP2_VCCR") (class "Default")
      (node (ref "C25") (pin "1") (pinfunction "1_1") (pintype "passive"))
      (node (ref "C27") (pin "2") (pinfunction "2_2") (pintype "passive"))
      (node (ref "C28") (pin "1") (pinfunction "1_1") (pintype "passive"))
      (node (ref "FB3") (pin "2") (pinfunction "2_2") (pintype "passive"))
      (node (ref "J5") (pin "P2_15") (pinfunction "P2_15_P2_15") (pintype "passive"))
    )
    (net (code "36") (name "SFP2_VCCT") (class "Default")
      (node (ref "C33") (pin "1") (pinfunction "1_1") (pintype "passive"))
      (node (ref "C34") (pin "2") (pinfunction "2_2") (pintype "passive"))
      (node (ref "C35") (pin "1") (pinfunction "1_1") (pintype "passive"))
      (node (ref "FB4") (pin "2") (pinfunction "2_2") (pintype "passive"))
      (node (ref "J5") (pin "P2_16") (pinfunction "P2_16_P2_16") (pintype "passive"))
    )
    (net (code "37") (name "unconnected-(J1-Pad1)") (class "Default")
      (node (ref "J1") (pin "1") (pinfunction "1_1") (pintype "passive"))
    )
    (net (code "38") (name "unconnected-(J1-Pad2)") (class "Default")
      (node (ref "J1") (pin "2") (pinfunction "2_2") (pintype "passive"))
    )
    (net (code "39") (name "unconnected-(J1-Pad3)") (class "Default")
      (node (ref "J1") (pin "3") (pinfunction "3_3") (pintype "passive"))
    )
    (net (code "40") (name "unconnected-(J1-Pad4)") (class "Default")
      (node (ref "J1") (pin "4") (pinfunction "4_4") (pintype "passive"))
    )
    (net (code "41") (name "unconnected-(J1-Pad5)") (class "Default")
      (node (ref "J1") (pin "5") (pinfunction "5_5") (pintype "passive"))
    )
    (net (code "42") (name "unconnected-(J1-Pad6)") (class "Default")
      (node (ref "J1") (pin "6") (pinfunction "6_6") (pintype "passive"))
    )
    (net (code "43") (name "unconnected-(J1-Pad7)") (class "Default")
      (node (ref "J1") (pin "7") (pinfunction "7_7") (pintype "passive"))
    )
    (net (code "44") (name "unconnected-(J1-Pad8)") (class "Default")
      (node (ref "J1") (pin "8") (pinfunction "8_8") (pintype "passive"))
    )
    (net (code "45") (name "unconnected-(J1-Pad9)") (class "Default")
      (node (ref "J1") (pin "9") (pinfunction "9_9") (pintype "passive"))
    )
    (net (code "46") (name "unconnected-(J1-Pad10)") (class "Default")
      (node (ref "J1") (pin "10") (pinfunction "10_10") (pintype "passive"))
    )
    (net (code "47") (name "unconnected-(J1-Pad11)") (class "Default")
      (node (ref "J1") (pin "11") (pinfunction "11_11") (pintype "passive"))
    )
    (net (code "48") (name "unconnected-(J1-Pad12)") (class "Default")
      (node (ref "J1") (pin "12") (pinfunction "12_12") (pintype "passive"))
    )
    (net (code "49") (name "unconnected-(J1-Pad13)") (class "Default")
      (node (ref "J1") (pin "13") (pinfunction "13_13") (pintype "passive"))
    )
    (net (code "50") (name "unconnected-(J1-Pad14)") (class "Default")
      (node (ref "J1") (pin "14") (pinfunction "14_14") (pintype "passive"))
    )
    (net (code "51") (name "unconnected-(J1-Pad15)") (class "Default")
      (node (ref "J1") (pin "15") (pinfunction "15_15") (pintype "passive"))
    )
    (net (code "52") (name "unconnected-(J1-Pad16)") (class "Default")
      (node (ref "J1") (pin "16") (pinfunction "16_16") (pintype "passive"))
    )
    (net (code "53") (name "unconnected-(J1-Pad17)") (class "Default")
      (node (ref "J1") (pin "17") (pinfunction "17_17") (pintype "passive"))
    )
    (net (code "54") (name "unconnected-(J1-Pad18)") (class "Default")
      (node (ref "J1") (pin "18") (pinfunction "18_18") (pintype "passive"))
    )
    (net (code "55") (name "unconnected-(J1-Pad19)") (class "Default")
      (node (ref "J1") (pin "19") (pinfunction "19_19") (pintype "passive"))
    )
    (net (code "56") (name "unconnected-(J1-Pad20)") (class "Default")
      (node (ref "J1") (pin "20") (pinfunction "20_20") (pintype "passive"))
    )
    (net (code "57") (name "unconnected-(J6-Pad1)") (class "Default")
      (node (ref "J6") (pin "1") (pinfunction "1_1") (pintype "passive"))
    )
    (net (code "58") (name "unconnected-(J6-Pad2)") (class "Default")
      (node (ref "J6") (pin "2") (pinfunction "2_2") (pintype "passive"))
    )
    (net (code "59") (name "unconnected-(J6-Pad3)") (class "Default")
      (node (ref "J6") (pin "3") (pinfunction "3_3") (pintype "passive"))
    )
    (net (code "60") (name "unconnected-(J6-Pad4)") (class "Default")
      (node (ref "J6") (pin "4") (pinfunction "4_4") (pintype "passive"))
    )
    (net (code "61") (name "unconnected-(J6-Pad5)") (class "Default")
      (node (ref "J6") (pin "5") (pinfunction "5_5") (pintype "passive"))
    )
    (net (code "62") (name "unconnected-(J6-Pad6)") (class "Default")
      (node (ref "J6") (pin "6") (pinfunction "6_6") (pintype "passive"))
    )
    (net (code "63") (name "unconnected-(J6-Pad7)") (class "Default")
      (node (ref "J6") (pin "7") (pinfunction "7_7") (pintype "passive"))
    )
    (net (code "64") (name "unconnected-(J6-Pad8)") (class "Default")
      (node (ref "J6") (pin "8") (pinfunction "8_8") (pintype "passive"))
    )
    (net (code "65") (name "unconnected-(J6-Pad9)") (class "Default")
      (node (ref "J6") (pin "9") (pinfunction "9_9") (pintype "passive"))
    )
    (net (code "66") (name "unconnected-(J6-Pad10)") (class "Default")
      (node (ref "J6") (pin "10") (pinfunction "10_10") (pintype "passive"))
    )
    (net (code "67") (name "unconnected-(J6-Pad11)") (class "Default")
      (node (ref "J6") (pin "11") (pinfunction "11_11") (pintype "passive"))
    )
    (net (code "68") (name "unconnected-(J6-Pad12)") (class "Default")
      (node (ref "J6") (pin "12") (pinfunction "12_12") (pintype "passive"))
    )
    (net (code "69") (name "unconnected-(J6-Pad13)") (class "Default")
      (node (ref "J6") (pin "13") (pinfunction "13_13") (pintype "passive"))
    )
    (net (code "70") (name "unconnected-(J6-Pad14)") (class "Default")
      (node (ref "J6") (pin "14") (pinfunction "14_14") (pintype "passive"))
    )
    (net (code "71") (name "unconnected-(J6-Pad15)") (class "Default")
      (node (ref "J6") (pin "15") (pinfunction "15_15") (pintype "passive"))
    )
    (net (code "72") (name "unconnected-(J6-Pad16)") (class "Default")
      (node (ref "J6") (pin "16") (pinfunction "16_16") (pintype "passive"))
    )
    (net (code "73") (name "unconnected-(J6-Pad17)") (class "Default")
      (node (ref "J6") (pin "17") (pinfunction "17_17") (pintype "passive"))
    )
    (net (code "74") (name "unconnected-(J6-Pad18)") (class "Default")
      (node (ref "J6") (pin "18") (pinfunction "18_18") (pintype "passive"))
    )
    (net (code "75") (name "unconnected-(J6-Pad19)") (class "Default")
      (node (ref "J6") (pin "19") (pinfunction "19_19") (pintype "passive"))
    )
    (net (code "76") (name "unconnected-(J6-Pad20)") (class "Default")
      (node (ref "J6") (pin "20") (pinfunction "20_20") (pintype "passive"))
    )
  )
)
